# STM32.net
KiCad netlist of a schematic drawn in Altium Designer
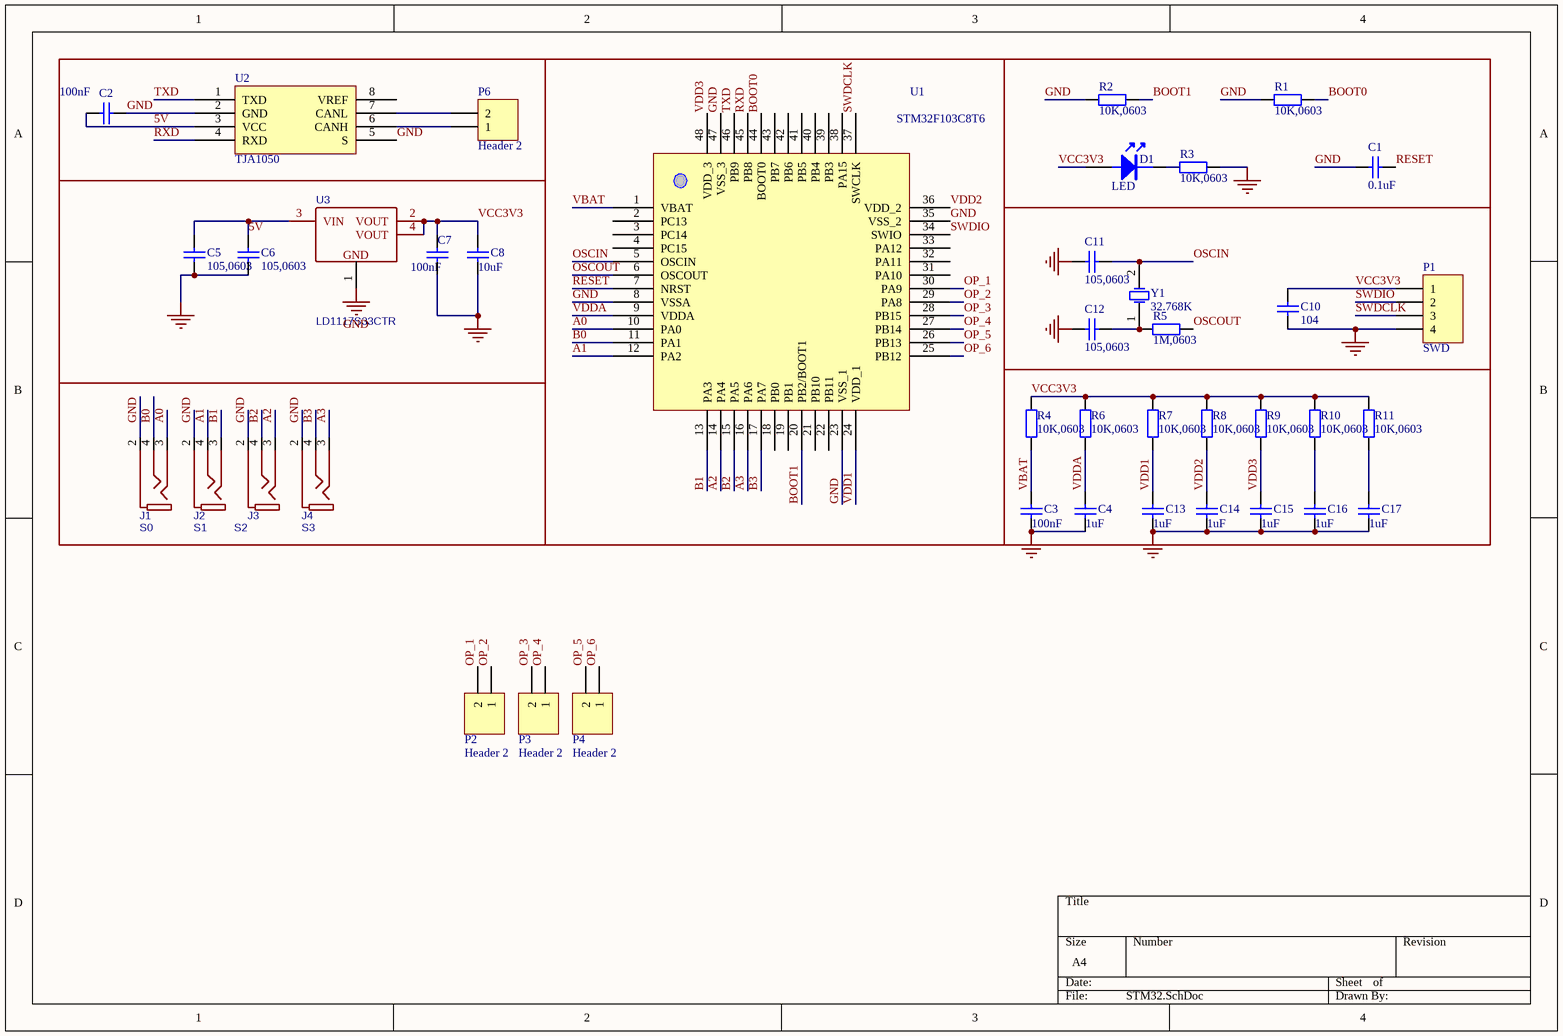
[diagram p0: STM32.SchDoc]

(export (version "E")
  (design (tool "Eeschema 10.0.6"))
  (components
    (comp (ref "C1")
      (value "0.1uF")
      (footprint "0805")
      (description "Capacitor")
      (fields (field (name "PUBLISHER") "Altium Limited"))
      (libsource (lib "Proje01") (part "Cap"))
    )
    (comp (ref "C2")
      (value "100nF")
      (footprint "0805")
      (description "Capacitor")
      (fields (field (name "PUBLISHER") "Altium Limited"))
      (libsource (lib "Proje01") (part "Cap"))
    )
    (comp (ref "C3")
      (value "100nF")
      (footprint "0805")
      (description "Capacitor")
      (fields (field (name "PUBLISHER") "Altium Limited"))
      (libsource (lib "Proje01") (part "Cap"))
    )
    (comp (ref "C4")
      (value "1uF")
      (footprint "0805")
      (description "Capacitor")
      (fields (field (name "PUBLISHER") "Altium Limited"))
      (libsource (lib "Proje01") (part "Cap"))
    )
    (comp (ref "C5")
      (value "105,0603")
      (footprint "0805")
      (description "Capacitor")
      (fields (field (name "PUBLISHER") "Altium Limited"))
      (libsource (lib "Proje01") (part "Cap"))
    )
    (comp (ref "C6")
      (value "105,0603")
      (footprint "0805")
      (description "Capacitor")
      (fields (field (name "PUBLISHER") "Altium Limited"))
      (libsource (lib "Proje01") (part "Cap"))
    )
    (comp (ref "C7")
      (value "100nF")
      (footprint "0805")
      (description "Capacitor")
      (fields (field (name "PUBLISHER") "Altium Limited"))
      (libsource (lib "Proje01") (part "Cap"))
    )
    (comp (ref "C8")
      (value "10uF")
      (footprint "0805")
      (description "Capacitor")
      (fields (field (name "Comment") "105,0603") (field (name "PUBLISHER") "Altium Limited"))
      (libsource (lib "Proje01") (part "Cap"))
    )
    (comp (ref "C10")
      (value "104")
      (footprint "0805")
      (description "Capacitor")
      (fields (field (name "PUBLISHER") "Altium Limited"))
      (libsource (lib "Proje01") (part "Cap"))
    )
    (comp (ref "C11")
      (value "105,0603")
      (footprint "0805")
      (description "Capacitor")
      (fields (field (name "PUBLISHER") "Altium Limited"))
      (libsource (lib "Proje01") (part "Cap"))
    )
    (comp (ref "C12")
      (value "105,0603")
      (footprint "0805")
      (description "Capacitor")
      (fields (field (name "PUBLISHER") "Altium Limited"))
      (libsource (lib "Proje01") (part "Cap"))
    )
    (comp (ref "C13")
      (value "1uF")
      (footprint "0805")
      (description "Capacitor")
      (fields (field (name "PUBLISHER") "Altium Limited"))
      (libsource (lib "Proje01") (part "Cap"))
    )
    (comp (ref "C14")
      (value "1uF")
      (footprint "0805")
      (description "Capacitor")
      (fields (field (name "PUBLISHER") "Altium Limited"))
      (libsource (lib "Proje01") (part "Cap"))
    )
    (comp (ref "C15")
      (value "1uF")
      (footprint "0805")
      (description "Capacitor")
      (fields (field (name "PUBLISHER") "Altium Limited"))
      (libsource (lib "Proje01") (part "Cap"))
    )
    (comp (ref "C16")
      (value "1uF")
      (footprint "0805")
      (description "Capacitor")
      (fields (field (name "PUBLISHER") "Altium Limited"))
      (libsource (lib "Proje01") (part "Cap"))
    )
    (comp (ref "C17")
      (value "1uF")
      (footprint "0805")
      (description "Capacitor")
      (fields (field (name "PUBLISHER") "Altium Limited"))
      (libsource (lib "Proje01") (part "Cap"))
    )
    (comp (ref "D1") (value "LED") (footprint "LED") (libsource (lib "Proje01") (part "LED")))
    (comp (ref "J1")
      (value "S0")
      (footprint "AUDIO-PJ313D")
      (fields
        (field (name "BOM_MANUFACTURER PART") "Straight headphone jack")
        (field (name "BOM_SUPPLIER PART") "C18167")
      )
      (libsource (lib "Proje01") (part "Stereo-jack"))
    )
    (comp (ref "J2")
      (value "S1")
      (footprint "AUDIO-PJ313D")
      (fields
        (field (name "BOM_MANUFACTURER PART") "Straight headphone jack")
        (field (name "BOM_SUPPLIER PART") "C18167")
      )
      (libsource (lib "Proje01") (part "Stereo-jack"))
    )
    (comp (ref "J3")
      (value "S2")
      (footprint "AUDIO-PJ313D")
      (fields
        (field (name "BOM_MANUFACTURER PART") "Straight headphone jack")
        (field (name "BOM_SUPPLIER PART") "C18167")
      )
      (libsource (lib "Proje01") (part "Stereo-jack"))
    )
    (comp (ref "J4")
      (value "S3")
      (footprint "AUDIO-PJ313D")
      (fields
        (field (name "BOM_MANUFACTURER PART") "Straight headphone jack")
        (field (name "BOM_SUPPLIER PART") "C18167")
      )
      (libsource (lib "Proje01") (part "Stereo-jack"))
    )
    (comp (ref "P1")
      (value "SWD")
      (footprint "HDR1X4H")
      (description "Header, 4-Pin")
      (fields (field (name "PUBLISHER") "Altium Limited"))
      (libsource (lib "Proje01") (part "Header 4"))
    )
    (comp (ref "P2")
      (value "Header 2")
      (footprint "HDR1X2")
      (description "Header, 2-Pin")
      (fields (field (name "PUBLISHER") "Altium Limited"))
      (libsource (lib "Proje01") (part "Header 2"))
    )
    (comp (ref "P3")
      (value "Header 2")
      (footprint "HDR1X2")
      (description "Header, 2-Pin")
      (fields (field (name "PUBLISHER") "Altium Limited"))
      (libsource (lib "Proje01") (part "Header 2"))
    )
    (comp (ref "P4")
      (value "Header 2")
      (footprint "HDR1X2")
      (description "Header, 2-Pin")
      (fields (field (name "PUBLISHER") "Altium Limited"))
      (libsource (lib "Proje01") (part "Header 2"))
    )
    (comp (ref "P6")
      (value "Header 2")
      (footprint "HDR1X2")
      (description "Header, 2-Pin")
      (fields (field (name "PUBLISHER") "Altium Limited"))
      (libsource (lib "") (part "Header 2_1"))
    )
    (comp (ref "R1")
      (value "10K,0603")
      (footprint "0805")
      (description "Resistor")
      (fields (field (name "PUBLISHER") "Altium Limited"))
      (libsource (lib "") (part "Res2_1"))
    )
    (comp (ref "R2")
      (value "10K,0603")
      (footprint "0805")
      (description "Resistor")
      (fields (field (name "PUBLISHER") "Altium Limited"))
      (libsource (lib "") (part "Res2_1"))
    )
    (comp (ref "R3")
      (value "10K,0603")
      (footprint "0805")
      (description "Resistor")
      (fields (field (name "PUBLISHER") "Altium Limited"))
      (libsource (lib "") (part "Res2_1"))
    )
    (comp (ref "R4")
      (value "10K,0603")
      (footprint "0805")
      (description "Resistor")
      (fields (field (name "PUBLISHER") "Altium Limited"))
      (libsource (lib "Proje01") (part "Res2"))
    )
    (comp (ref "R5")
      (value "1M,0603")
      (footprint "0805")
      (description "Resistor")
      (fields (field (name "PUBLISHER") "Altium Limited"))
      (libsource (lib "") (part "Res2_2"))
    )
    (comp (ref "R6")
      (value "10K,0603")
      (footprint "0805")
      (description "Resistor")
      (fields (field (name "PUBLISHER") "Altium Limited"))
      (libsource (lib "Proje01") (part "Res2"))
    )
    (comp (ref "R7")
      (value "10K,0603")
      (footprint "0805")
      (description "Resistor")
      (fields (field (name "PUBLISHER") "Altium Limited"))
      (libsource (lib "Proje01") (part "Res2"))
    )
    (comp (ref "R8")
      (value "10K,0603")
      (footprint "0805")
      (description "Resistor")
      (fields (field (name "PUBLISHER") "Altium Limited"))
      (libsource (lib "Proje01") (part "Res2"))
    )
    (comp (ref "R9")
      (value "10K,0603")
      (footprint "0805")
      (description "Resistor")
      (fields (field (name "PUBLISHER") "Altium Limited"))
      (libsource (lib "Proje01") (part "Res2"))
    )
    (comp (ref "R10")
      (value "10K,0603")
      (footprint "0805")
      (description "Resistor")
      (fields (field (name "PUBLISHER") "Altium Limited"))
      (libsource (lib "Proje01") (part "Res2"))
    )
    (comp (ref "R11")
      (value "10K,0603")
      (footprint "0805")
      (description "Resistor")
      (fields (field (name "PUBLISHER") "Altium Limited"))
      (libsource (lib "Proje01") (part "Res2"))
    )
    (comp (ref "U1")
      (value "STM32F103C8T6")
      (footprint "48P")
      (libsource (lib "Proje01") (part "STM32F103C8T6"))
    )
    (comp (ref "U2")
      (value "TJA1050")
      (footprint "SOIC-8_150MIL")
      (libsource (lib "Proje01") (part "TJA1050"))
    )
    (comp (ref "U3")
      (value "LD1117S33CTR")
      (footprint "SOT-223")
      (fields (field (name "BOM_SUPPLIER PART") "C35879"))
      (libsource (lib "Proje01") (part "LD1117S33CTR"))
    )
    (comp (ref "Y1")
      (value "32.768K")
      (footprint "XTAL1")
      (description "Crystal Oscillator")
      (fields (field (name "PUBLISHER") "Altium Limited"))
      (libsource (lib "Proje01") (part "XTAL"))
    )
  )
  (nets
    (net (code "1") (name "/5V") (class "Default")
      (node (ref "C2") (pin "2") (pinfunction "2_2") (pintype "passive"))
      (node (ref "C5") (pin "2") (pinfunction "2_2") (pintype "passive"))
      (node (ref "C6") (pin "2") (pinfunction "2_2") (pintype "passive"))
      (node (ref "U2") (pin "3") (pinfunction "VCC_3") (pintype "passive"))
      (node (ref "U3") (pin "3") (pinfunction "VIN_3") (pintype "passive"))
    )
    (net (code "2") (name "/A0") (class "Default")
      (node (ref "J1") (pin "3") (pinfunction "3_3") (pintype "passive"))
      (node (ref "U1") (pin "10") (pinfunction "PA0_10") (pintype "passive"))
    )
    (net (code "3") (name "/A1") (class "Default")
      (node (ref "J2") (pin "4") (pinfunction "4_4") (pintype "passive"))
      (node (ref "U1") (pin "12") (pinfunction "PA2_12") (pintype "passive"))
    )
    (net (code "4") (name "/A2") (class "Default")
      (node (ref "J3") (pin "3") (pinfunction "3_3") (pintype "passive"))
      (node (ref "U1") (pin "14") (pinfunction "PA4_14") (pintype "passive"))
    )
    (net (code "5") (name "/A3") (class "Default")
      (node (ref "J4") (pin "3") (pinfunction "3_3") (pintype "passive"))
      (node (ref "U1") (pin "16") (pinfunction "PA6_16") (pintype "passive"))
    )
    (net (code "6") (name "/B0") (class "Default")
      (node (ref "J1") (pin "4") (pinfunction "4_4") (pintype "passive"))
      (node (ref "U1") (pin "11") (pinfunction "PA1_11") (pintype "passive"))
    )
    (net (code "7") (name "/B1") (class "Default")
      (node (ref "J2") (pin "3") (pinfunction "3_3") (pintype "passive"))
      (node (ref "U1") (pin "13") (pinfunction "PA3_13") (pintype "passive"))
    )
    (net (code "8") (name "/B2") (class "Default")
      (node (ref "J3") (pin "4") (pinfunction "4_4") (pintype "passive"))
      (node (ref "U1") (pin "15") (pinfunction "PA5_15") (pintype "passive"))
    )
    (net (code "9") (name "/B3") (class "Default")
      (node (ref "J4") (pin "4") (pinfunction "4_4") (pintype "passive"))
      (node (ref "U1") (pin "17") (pinfunction "PA7_17") (pintype "passive"))
    )
    (net (code "10") (name "/BOOT0") (class "Default")
      (node (ref "R1") (pin "2") (pinfunction "2_2") (pintype "passive"))
      (node (ref "U1") (pin "44") (pinfunction "BOOT0_44") (pintype "passive"))
    )
    (net (code "11") (name "/BOOT1") (class "Default")
      (node (ref "R2") (pin "2") (pinfunction "2_2") (pintype "passive"))
      (node (ref "U1") (pin "20") (pinfunction "PB2/BOOT1_20") (pintype "passive"))
    )
    (net (code "12") (name "/OP_1") (class "Default")
      (node (ref "P2") (pin "2") (pinfunction "2_2") (pintype "passive"))
      (node (ref "U1") (pin "30") (pinfunction "PA9_30") (pintype "passive"))
    )
    (net (code "13") (name "/OP_2") (class "Default")
      (node (ref "P2") (pin "1") (pinfunction "1_1") (pintype "passive"))
      (node (ref "U1") (pin "29") (pinfunction "PA8_29") (pintype "passive"))
    )
    (net (code "14") (name "/OP_3") (class "Default")
      (node (ref "P3") (pin "2") (pinfunction "2_2") (pintype "passive"))
      (node (ref "U1") (pin "28") (pinfunction "PB15_28") (pintype "passive"))
    )
    (net (code "15") (name "/OP_4") (class "Default")
      (node (ref "P3") (pin "1") (pinfunction "1_1") (pintype "passive"))
      (node (ref "U1") (pin "27") (pinfunction "PB14_27") (pintype "passive"))
    )
    (net (code "16") (name "/OP_5") (class "Default")
      (node (ref "P4") (pin "2") (pinfunction "2_2") (pintype "passive"))
      (node (ref "U1") (pin "26") (pinfunction "PB13_26") (pintype "passive"))
    )
    (net (code "17") (name "/OP_6") (class "Default")
      (node (ref "P4") (pin "1") (pinfunction "1_1") (pintype "passive"))
      (node (ref "U1") (pin "25") (pinfunction "PB12_25") (pintype "passive"))
    )
    (net (code "18") (name "/OSCIN") (class "Default")
      (node (ref "C11") (pin "2") (pinfunction "2_2") (pintype "passive"))
      (node (ref "U1") (pin "5") (pinfunction "OSCIN_5") (pintype "passive"))
      (node (ref "Y1") (pin "2") (pinfunction "OSC2_2") (pintype "passive"))
    )
    (net (code "19") (name "/OSCOUT") (class "Default")
      (node (ref "R5") (pin "1") (pinfunction "1_1") (pintype "passive"))
      (node (ref "U1") (pin "6") (pinfunction "OSCOUT_6") (pintype "passive"))
    )
    (net (code "20") (name "/RESET") (class "Default")
      (node (ref "C1") (pin "2") (pinfunction "2_2") (pintype "passive"))
      (node (ref "U1") (pin "7") (pinfunction "NRST_7") (pintype "passive"))
    )
    (net (code "21") (name "/RXD") (class "Default")
      (node (ref "U1") (pin "45") (pinfunction "PB8_45") (pintype "passive"))
      (node (ref "U2") (pin "4") (pinfunction "RXD_4") (pintype "passive"))
    )
    (net (code "22") (name "/SWDCLK") (class "Default")
      (node (ref "P1") (pin "3") (pinfunction "3_3") (pintype "passive"))
      (node (ref "U1") (pin "37") (pinfunction "SWCLK_37") (pintype "passive"))
    )
    (net (code "23") (name "/SWDIO") (class "Default")
      (node (ref "P1") (pin "2") (pinfunction "2_2") (pintype "passive"))
      (node (ref "U1") (pin "34") (pinfunction "SWIO_34") (pintype "passive"))
    )
    (net (code "24") (name "/TXD") (class "Default")
      (node (ref "U1") (pin "46") (pinfunction "PB9_46") (pintype "passive"))
      (node (ref "U2") (pin "1") (pinfunction "TXD_1") (pintype "passive"))
    )
    (net (code "25") (name "/VBAT") (class "Default")
      (node (ref "C3") (pin "2") (pinfunction "2_2") (pintype "passive"))
      (node (ref "R4") (pin "1") (pinfunction "1_1") (pintype "passive"))
      (node (ref "U1") (pin "1") (pinfunction "VBAT_1") (pintype "passive"))
    )
    (net (code "26") (name "/VCC3V3") (class "Default")
      (node (ref "C10") (pin "2") (pinfunction "2_2") (pintype "passive"))
      (node (ref "C7") (pin "2") (pinfunction "2_2") (pintype "passive"))
      (node (ref "C8") (pin "2") (pinfunction "2_2") (pintype "passive"))
      (node (ref "D1") (pin "A") (pinfunction "1_A") (pintype "passive"))
      (node (ref "P1") (pin "1") (pinfunction "1_1") (pintype "passive"))
      (node (ref "R10") (pin "2") (pinfunction "2_2") (pintype "passive"))
      (node (ref "R11") (pin "2") (pinfunction "2_2") (pintype "passive"))
      (node (ref "R4") (pin "2") (pinfunction "2_2") (pintype "passive"))
      (node (ref "R6") (pin "2") (pinfunction "2_2") (pintype "passive"))
      (node (ref "R7") (pin "2") (pinfunction "2_2") (pintype "passive"))
      (node (ref "R8") (pin "2") (pinfunction "2_2") (pintype "passive"))
      (node (ref "R9") (pin "2") (pinfunction "2_2") (pintype "passive"))
      (node (ref "U3") (pin "2") (pinfunction "VOUT_2") (pintype "passive"))
      (node (ref "U3") (pin "4") (pinfunction "VOUT_4") (pintype "passive"))
    )
    (net (code "27") (name "/VDD1") (class "Default")
      (node (ref "C13") (pin "2") (pinfunction "2_2") (pintype "passive"))
      (node (ref "R7") (pin "1") (pinfunction "1_1") (pintype "passive"))
      (node (ref "U1") (pin "24") (pinfunction "VDD_1_24") (pintype "passive"))
    )
    (net (code "28") (name "/VDD2") (class "Default")
      (node (ref "C14") (pin "2") (pinfunction "2_2") (pintype "passive"))
      (node (ref "R8") (pin "1") (pinfunction "1_1") (pintype "passive"))
      (node (ref "U1") (pin "36") (pinfunction "VDD_2_36") (pintype "passive"))
    )
    (net (code "29") (name "/VDD3") (class "Default")
      (node (ref "C15") (pin "2") (pinfunction "2_2") (pintype "passive"))
      (node (ref "R9") (pin "1") (pinfunction "1_1") (pintype "passive"))
      (node (ref "U1") (pin "48") (pinfunction "VDD_3_48") (pintype "passive"))
    )
    (net (code "30") (name "/VDDA") (class "Default")
      (node (ref "C4") (pin "2") (pinfunction "2_2") (pintype "passive"))
      (node (ref "R6") (pin "1") (pinfunction "1_1") (pintype "passive"))
      (node (ref "U1") (pin "9") (pinfunction "VDDA_9") (pintype "passive"))
    )
    (net (code "31") (name "GND") (class "Default")
      (node (ref "C1") (pin "1") (pinfunction "1_1") (pintype "passive"))
      (node (ref "C10") (pin "1") (pinfunction "1_1") (pintype "passive"))
      (node (ref "C11") (pin "1") (pinfunction "1_1") (pintype "passive"))
      (node (ref "C12") (pin "1") (pinfunction "1_1") (pintype "passive"))
      (node (ref "C13") (pin "1") (pinfunction "1_1") (pintype "passive"))
      (node (ref "C14") (pin "1") (pinfunction "1_1") (pintype "passive"))
      (node (ref "C15") (pin "1") (pinfunction "1_1") (pintype "passive"))
      (node (ref "C16") (pin "1") (pinfunction "1_1") (pintype "passive"))
      (node (ref "C17") (pin "1") (pinfunction "1_1") (pintype "passive"))
      (node (ref "C2") (pin "1") (pinfunction "1_1") (pintype "passive"))
      (node (ref "C3") (pin "1") (pinfunction "1_1") (pintype "passive"))
      (node (ref "C4") (pin "1") (pinfunction "1_1") (pintype "passive"))
      (node (ref "C5") (pin "1") (pinfunction "1_1") (pintype "passive"))
      (node (ref "C6") (pin "1") (pinfunction "1_1") (pintype "passive"))
      (node (ref "C7") (pin "1") (pinfunction "1_1") (pintype "passive"))
      (node (ref "C8") (pin "1") (pinfunction "1_1") (pintype "passive"))
      (node (ref "J1") (pin "2") (pinfunction "2_2") (pintype "passive"))
      (node (ref "J2") (pin "2") (pinfunction "2_2") (pintype "passive"))
      (node (ref "J3") (pin "2") (pinfunction "2_2") (pintype "passive"))
      (node (ref "J4") (pin "2") (pinfunction "2_2") (pintype "passive"))
      (node (ref "P1") (pin "4") (pinfunction "4_4") (pintype "passive"))
      (node (ref "R1") (pin "1") (pinfunction "1_1") (pintype "passive"))
      (node (ref "R2") (pin "1") (pinfunction "1_1") (pintype "passive"))
      (node (ref "R3") (pin "2") (pinfunction "2_2") (pintype "passive"))
      (node (ref "U1") (pin "23") (pinfunction "VSS_1_23") (pintype "passive"))
      (node (ref "U1") (pin "35") (pinfunction "VSS_2_35") (pintype "passive"))
      (node (ref "U1") (pin "47") (pinfunction "VSS_3_47") (pintype "passive"))
      (node (ref "U1") (pin "8") (pinfunction "VSSA_8") (pintype "passive"))
      (node (ref "U2") (pin "2") (pinfunction "GND_2") (pintype "passive"))
      (node (ref "U2") (pin "5") (pinfunction "S_5") (pintype "passive"))
      (node (ref "U3") (pin "1") (pinfunction "GND_1") (pintype "passive"))
    )
    (net (code "32") (name "Net-(C16-Pad2)") (class "Default")
      (node (ref "C16") (pin "2") (pinfunction "2_2") (pintype "passive"))
      (node (ref "R10") (pin "1") (pinfunction "1_1") (pintype "passive"))
    )
    (net (code "33") (name "Net-(C17-Pad2)") (class "Default")
      (node (ref "C17") (pin "2") (pinfunction "2_2") (pintype "passive"))
      (node (ref "R11") (pin "1") (pinfunction "1_1") (pintype "passive"))
    )
    (net (code "34") (name "Net-(D1-2)") (class "Default")
      (node (ref "D1") (pin "K") (pinfunction "2_K") (pintype "passive"))
      (node (ref "R3") (pin "1") (pinfunction "1_1") (pintype "passive"))
    )
    (net (code "35") (name "Net-(U2-CANH)") (class "Default")
      (node (ref "P6") (pin "1") (pinfunction "1_1") (pintype "passive"))
      (node (ref "U2") (pin "6") (pinfunction "CANH_6") (pintype "passive"))
    )
    (net (code "36") (name "Net-(U2-CANL)") (class "Default")
      (node (ref "P6") (pin "2") (pinfunction "2_2") (pintype "passive"))
      (node (ref "U2") (pin "7") (pinfunction "CANL_7") (pintype "passive"))
    )
    (net (code "37") (name "Net-(Y1-OSC1)") (class "Default")
      (node (ref "C12") (pin "2") (pinfunction "2_2") (pintype "passive"))
      (node (ref "R5") (pin "2") (pinfunction "2_2") (pintype "passive"))
      (node (ref "Y1") (pin "1") (pinfunction "OSC1_1") (pintype "passive"))
    )
    (net (code "38") (name "unconnected-(U1-PA10-Pad31)") (class "Default")
      (node (ref "U1") (pin "31") (pinfunction "PA10_31") (pintype "passive"))
    )
    (net (code "39") (name "unconnected-(U1-PA11-Pad32)") (class "Default")
      (node (ref "U1") (pin "32") (pinfunction "PA11_32") (pintype "passive"))
    )
    (net (code "40") (name "unconnected-(U1-PA12-Pad33)") (class "Default")
      (node (ref "U1") (pin "33") (pinfunction "PA12_33") (pintype "passive"))
    )
    (net (code "41") (name "unconnected-(U1-PA15-Pad38)") (class "Default")
      (node (ref "U1") (pin "38") (pinfunction "PA15_38") (pintype "passive"))
    )
    (net (code "42") (name "unconnected-(U1-PB0-Pad18)") (class "Default")
      (node (ref "U1") (pin "18") (pinfunction "PB0_18") (pintype "passive"))
    )
    (net (code "43") (name "unconnected-(U1-PB1-Pad19)") (class "Default")
      (node (ref "U1") (pin "19") (pinfunction "PB1_19") (pintype "passive"))
    )
    (net (code "44") (name "unconnected-(U1-PB3-Pad39)") (class "Default")
      (node (ref "U1") (pin "39") (pinfunction "PB3_39") (pintype "passive"))
    )
    (net (code "45") (name "unconnected-(U1-PB4-Pad40)") (class "Default")
      (node (ref "U1") (pin "40") (pinfunction "PB4_40") (pintype "passive"))
    )
    (net (code "46") (name "unconnected-(U1-PB5-Pad41)") (class "Default")
      (node (ref "U1") (pin "41") (pinfunction "PB5_41") (pintype "passive"))
    )
    (net (code "47") (name "unconnected-(U1-PB6-Pad42)") (class "Default")
      (node (ref "U1") (pin "42") (pinfunction "PB6_42") (pintype "passive"))
    )
    (net (code "48") (name "unconnected-(U1-PB7-Pad43)") (class "Default")
      (node (ref "U1") (pin "43") (pinfunction "PB7_43") (pintype "passive"))
    )
    (net (code "49") (name "unconnected-(U1-PB10-Pad21)") (class "Default")
      (node (ref "U1") (pin "21") (pinfunction "PB10_21") (pintype "passive"))
    )
    (net (code "50") (name "unconnected-(U1-PB11-Pad22)") (class "Default")
      (node (ref "U1") (pin "22") (pinfunction "PB11_22") (pintype "passive"))
    )
    (net (code "51") (name "unconnected-(U1-PC13-Pad2)") (class "Default")
      (node (ref "U1") (pin "2") (pinfunction "PC13_2") (pintype "passive"))
    )
    (net (code "52") (name "unconnected-(U1-PC14-Pad3)") (class "Default")
      (node (ref "U1") (pin "3") (pinfunction "PC14_3") (pintype "passive"))
    )
    (net (code "53") (name "unconnected-(U1-PC15-Pad4)") (class "Default")
      (node (ref "U1") (pin "4") (pinfunction "PC15_4") (pintype "passive"))
    )
    (net (code "54") (name "unconnected-(U2-VREF-Pad8)") (class "Default")
      (node (ref "U2") (pin "8") (pinfunction "VREF_8") (pintype "passive"))
    )
  )
)
